# HMLFO.net
KiCad netlist of a schematic drawn in EAGLE
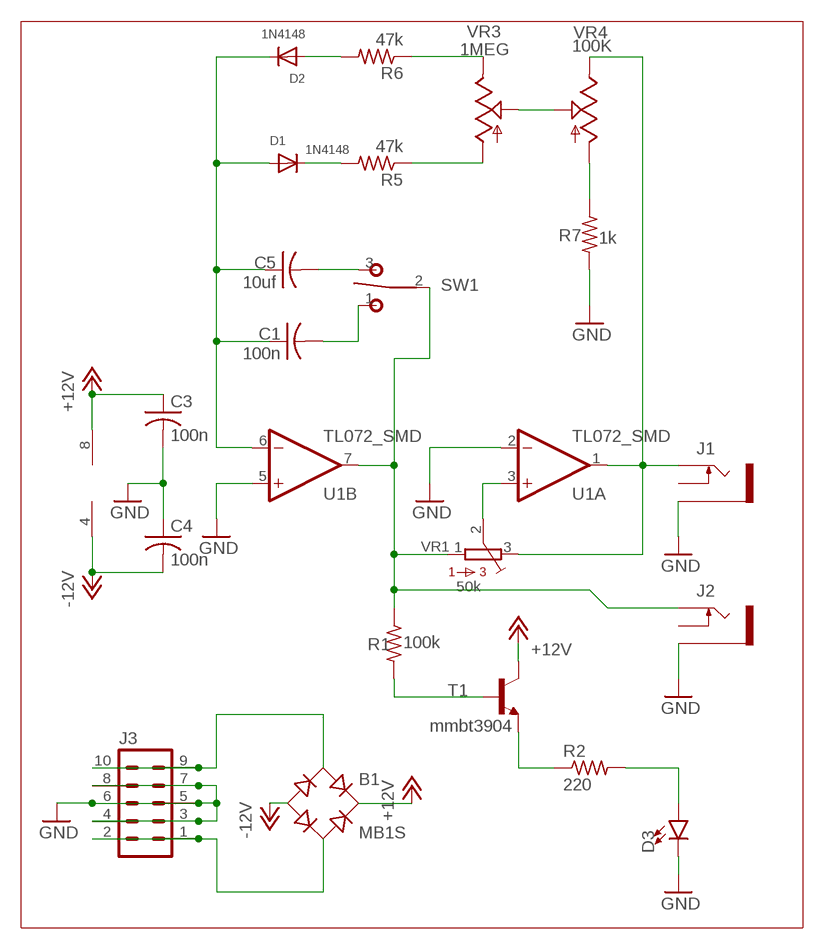
[diagram p0: schematic, sheet 1]

(export (version "E")
  (design (tool "Eeschema 10.0.6"))
  (components
    (comp (ref "B1")
      (value "MB1S")
      (footprint "eagle-import:SOIC-4")
      (libsource (lib "eagle-import") (part "MBS1"))
    )
    (comp (ref "C1")
      (value "100n")
      (footprint "eagle-import:C0603K")
      (libsource (lib "eagle-import") (part "C-USC0603K"))
    )
    (comp (ref "C3")
      (value "100n")
      (footprint "eagle-import:C0603K")
      (libsource (lib "eagle-import") (part "C-USC0603K"))
    )
    (comp (ref "C4")
      (value "100n")
      (footprint "eagle-import:C0603K")
      (libsource (lib "eagle-import") (part "C-USC0603K"))
    )
    (comp (ref "C5")
      (value "10uf")
      (footprint "eagle-import:C0805K")
      (libsource (lib "eagle-import") (part "C-USC0805K"))
    )
    (comp (ref "D1")
      (value "1N4148")
      (footprint "eagle-import:SOD-323F")
      (libsource (lib "eagle-import") (part "DIODESOD-323F"))
    )
    (comp (ref "D2")
      (value "1N4148")
      (footprint "eagle-import:SOD-323F")
      (libsource (lib "eagle-import") (part "DIODESOD-323F"))
    )
    (comp (ref "D3")
      (value "LED3MM")
      (footprint "eagle-import:LED_3MM")
      (libsource (lib "eagle-import") (part "LED3MM"))
    )
    (comp (ref "J1")
      (value "THONKICONNNEW")
      (footprint "eagle-import:WQP-PJ301M-12_JACK")
      (libsource (lib "eagle-import") (part "THONKICONNNEW"))
    )
    (comp (ref "J2")
      (value "THONKICONNNEW")
      (footprint "eagle-import:WQP-PJ301M-12_JACK")
      (libsource (lib "eagle-import") (part "THONKICONNNEW"))
    )
    (comp (ref "J3")
      (value "MA05-2")
      (footprint "eagle-import:MA05-2")
      (libsource (lib "eagle-import") (part "MA05-2"))
    )
    (comp (ref "R1")
      (value "100k")
      (footprint "eagle-import:R0603")
      (libsource (lib "eagle-import") (part "R-US_R0603"))
    )
    (comp (ref "R2")
      (value "220")
      (footprint "eagle-import:R0603")
      (libsource (lib "eagle-import") (part "R-US_R0603"))
    )
    (comp (ref "R5")
      (value "47k")
      (footprint "eagle-import:R0603")
      (libsource (lib "eagle-import") (part "R-US_R0603"))
    )
    (comp (ref "R6")
      (value "47k")
      (footprint "eagle-import:R0603")
      (libsource (lib "eagle-import") (part "R-US_R0603"))
    )
    (comp (ref "R7")
      (value "1k")
      (footprint "eagle-import:R0603")
      (libsource (lib "eagle-import") (part "R-US_R0603"))
    )
    (comp (ref "SW1")
      (value "T-80-T-SPDT-ON-OFF-ON")
      (footprint "eagle-import:M9040P")
      (libsource (lib "eagle-import") (part "T-80-T-SPDT-ON-OFF-ON"))
    )
    (comp (ref "T1")
      (value "mmbt3904")
      (footprint "eagle-import:SOT23-BEC")
      (libsource (lib "eagle-import") (part "-NPN-SOT23-BECMMBT3904LT1"))
    )
    (comp (ref "U1")
      (value "TL072_SMD")
      (footprint "eagle-import:SO08")
      (libsource (lib "eagle-import") (part "TL072_SMD"))
    )
    (comp (ref "VR1")
      (value "50k")
      (footprint "eagle-import:BOURNS_3362P_TRIMMER")
      (libsource (lib "eagle-import") (part "BOURNS_3362P_TRIMMERP"))
    )
    (comp (ref "VR3")
      (value "1MEG")
      (footprint "eagle-import:9MM_SNAP-IN_POT")
      (libsource (lib "eagle-import") (part "9MM_SNAP-IN_POT_"))
    )
    (comp (ref "VR4")
      (value "100K")
      (footprint "eagle-import:9MM_SNAP-IN_POT")
      (libsource (lib "eagle-import") (part "9MM_SNAP-IN_POT_"))
    )
  )
  (nets
    (net (code "1") (name "+12V") (class "Default")
      (node (ref "B1") (pin "+") (pinfunction "+_+") (pintype "passive"))
      (node (ref "C3") (pin "1") (pinfunction "1_1") (pintype "passive"))
      (node (ref "T1") (pin "C") (pinfunction "C_C") (pintype "passive"))
      (node (ref "U1") (pin "8") (pinfunction "V+_8") (pintype "power_in"))
    )
    (net (code "2") (name "-12V") (class "Default")
      (node (ref "B1") (pin "-") (pinfunction "-_-") (pintype "passive"))
      (node (ref "C4") (pin "2") (pinfunction "2_2") (pintype "passive"))
      (node (ref "U1") (pin "4") (pinfunction "V-_4") (pintype "power_in"))
    )
    (net (code "3") (name "GND") (class "Default")
      (node (ref "C3") (pin "2") (pinfunction "2_2") (pintype "passive"))
      (node (ref "C4") (pin "1") (pinfunction "1_1") (pintype "passive"))
      (node (ref "D3") (pin "K") (pinfunction "C_K") (pintype "passive"))
      (node (ref "J1") (pin "P$3_SLEEVE") (pinfunction "SLEEVE_P$3_SLEEVE") (pintype "passive"))
      (node (ref "J2") (pin "P$3_SLEEVE") (pinfunction "SLEEVE_P$3_SLEEVE") (pintype "passive"))
      (node (ref "J3") (pin "3") (pinfunction "3_3") (pintype "passive"))
      (node (ref "J3") (pin "4") (pinfunction "4_4") (pintype "passive"))
      (node (ref "J3") (pin "5") (pinfunction "5_5") (pintype "passive"))
      (node (ref "J3") (pin "6") (pinfunction "6_6") (pintype "passive"))
      (node (ref "J3") (pin "7") (pinfunction "7_7") (pintype "passive"))
      (node (ref "J3") (pin "8") (pinfunction "8_8") (pintype "passive"))
      (node (ref "R7") (pin "2") (pinfunction "2_2") (pintype "passive"))
      (node (ref "U1") (pin "2") (pinfunction "-IN_2") (pintype "input"))
      (node (ref "U1") (pin "5") (pinfunction "+IN_5") (pintype "input"))
    )
    (net (code "4") (name "Net-(B1-AC1)") (class "Default")
      (node (ref "B1") (pin "~1") (pinfunction "AC1_~1") (pintype "passive"))
      (node (ref "J3") (pin "10") (pinfunction "10_10") (pintype "passive"))
      (node (ref "J3") (pin "9") (pinfunction "9_9") (pintype "passive"))
    )
    (net (code "5") (name "Net-(B1-AC2)") (class "Default")
      (node (ref "B1") (pin "~2") (pinfunction "AC2_~2") (pintype "passive"))
      (node (ref "J3") (pin "1") (pinfunction "1_1") (pintype "passive"))
      (node (ref "J3") (pin "2") (pinfunction "2_2") (pintype "passive"))
    )
    (net (code "6") (name "Net-(D1-PadC)") (class "Default")
      (node (ref "D1") (pin "C") (pinfunction "C_C") (pintype "passive"))
      (node (ref "R5") (pin "2") (pinfunction "2_2") (pintype "passive"))
    )
    (net (code "7") (name "Net-(D2-PadA)") (class "Default")
      (node (ref "D2") (pin "A") (pinfunction "A_A") (pintype "passive"))
      (node (ref "R6") (pin "2") (pinfunction "2_2") (pintype "passive"))
    )
    (net (code "8") (name "Net-(D3-PadA)") (class "Default")
      (node (ref "D3") (pin "A") (pinfunction "A_A") (pintype "passive"))
      (node (ref "R2") (pin "2") (pinfunction "2_2") (pintype "passive"))
    )
    (net (code "9") (name "Net-(J1-TIP)") (class "Default")
      (node (ref "J1") (pin "P$1_TIP") (pinfunction "TIP_P$1_TIP") (pintype "passive"))
      (node (ref "U1") (pin "1") (pinfunction "OUT_1") (pintype "output"))
      (node (ref "VR1") (pin "3") (pinfunction "3_3") (pintype "passive"))
      (node (ref "VR4") (pin "3") (pinfunction "E_3") (pintype "passive"))
    )
    (net (code "10") (name "Net-(J2-TIP)") (class "Default")
      (node (ref "J2") (pin "P$1_TIP") (pinfunction "TIP_P$1_TIP") (pintype "passive"))
      (node (ref "R1") (pin "1") (pinfunction "1_1") (pintype "passive"))
      (node (ref "SW1") (pin "2") (pinfunction "P_2") (pintype "passive"))
      (node (ref "U1") (pin "7") (pinfunction "OUT_7") (pintype "output"))
      (node (ref "VR1") (pin "1") (pinfunction "1_1") (pintype "passive"))
    )
    (net (code "11") (name "Net-(R1-Pad2)") (class "Default")
      (node (ref "R1") (pin "2") (pinfunction "2_2") (pintype "passive"))
      (node (ref "T1") (pin "B") (pinfunction "B_B") (pintype "passive"))
    )
    (net (code "12") (name "Net-(R2-Pad1)") (class "Default")
      (node (ref "R2") (pin "1") (pinfunction "1_1") (pintype "passive"))
      (node (ref "T1") (pin "E") (pinfunction "E_E") (pintype "passive"))
    )
    (net (code "13") (name "Net-(SW1-O)") (class "Default")
      (node (ref "C1") (pin "2") (pinfunction "2_2") (pintype "passive"))
      (node (ref "SW1") (pin "1") (pinfunction "O_1") (pintype "passive"))
    )
    (net (code "14") (name "Net-(SW1-S)") (class "Default")
      (node (ref "C5") (pin "2") (pinfunction "2_2") (pintype "passive"))
      (node (ref "SW1") (pin "3") (pinfunction "S_3") (pintype "passive"))
    )
    (net (code "15") (name "Net-(U1A-+IN)") (class "Default")
      (node (ref "U1") (pin "3") (pinfunction "+IN_3") (pintype "input"))
      (node (ref "VR1") (pin "2") (pinfunction "2_2") (pintype "passive"))
    )
    (net (code "16") (name "Net-(U1B--IN)") (class "Default")
      (node (ref "C1") (pin "1") (pinfunction "1_1") (pintype "passive"))
      (node (ref "C5") (pin "1") (pinfunction "1_1") (pintype "passive"))
      (node (ref "D1") (pin "A") (pinfunction "A_A") (pintype "passive"))
      (node (ref "D2") (pin "C") (pinfunction "C_C") (pintype "passive"))
      (node (ref "U1") (pin "6") (pinfunction "-IN_6") (pintype "input"))
    )
    (net (code "17") (name "Net-(VR3-A)") (class "Default")
      (node (ref "R5") (pin "1") (pinfunction "1_1") (pintype "passive"))
      (node (ref "VR3") (pin "1") (pinfunction "A_1") (pintype "passive"))
    )
    (net (code "18") (name "Net-(VR3-E)") (class "Default")
      (node (ref "R6") (pin "1") (pinfunction "1_1") (pintype "passive"))
      (node (ref "VR3") (pin "3") (pinfunction "E_3") (pintype "passive"))
    )
    (net (code "19") (name "Net-(VR3-S)") (class "Default")
      (node (ref "VR3") (pin "2") (pinfunction "S_2") (pintype "passive"))
      (node (ref "VR4") (pin "2") (pinfunction "S_2") (pintype "passive"))
    )
    (net (code "20") (name "Net-(VR4-A)") (class "Default")
      (node (ref "R7") (pin "1") (pinfunction "1_1") (pintype "passive"))
      (node (ref "VR4") (pin "1") (pinfunction "A_1") (pintype "passive"))
    )
    (net (code "21") (name "unconnected-(J1-SWITCH-PadP$2_SWITCH)") (class "Default")
      (node (ref "J1") (pin "P$2_SWITCH") (pinfunction "SWITCH_P$2_SWITCH") (pintype "passive"))
    )
    (net (code "22") (name "unconnected-(J2-SWITCH-PadP$2_SWITCH)") (class "Default")
      (node (ref "J2") (pin "P$2_SWITCH") (pinfunction "SWITCH_P$2_SWITCH") (pintype "passive"))
    )
  )
)
